# RF315.net
KiCad netlist of a schematic drawn in Altium Designer
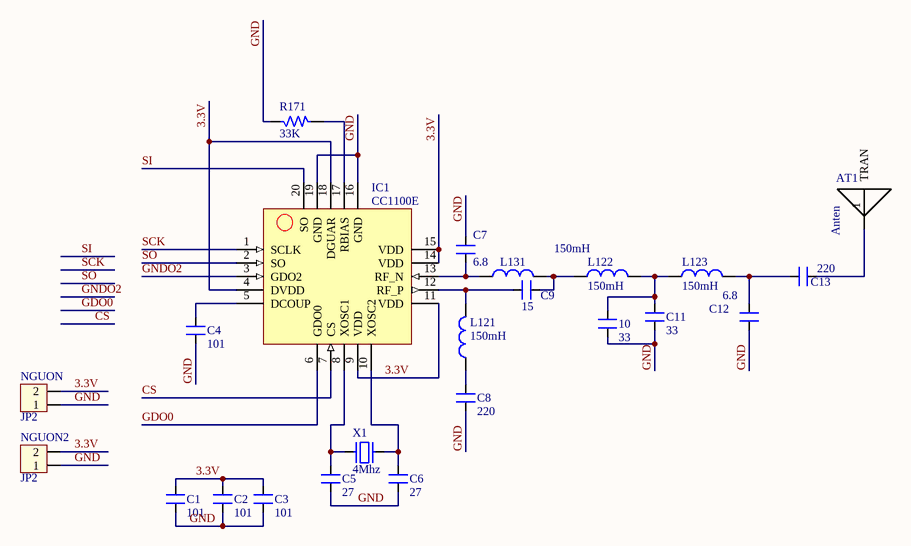
[diagram p0: RF315.SchDoc]

(export (version "E")
  (design (tool "Eeschema 10.0.6"))
  (components
    (comp (ref "10")
      (value "33")
      (footprint "SM-0805")
      (description "Cap SMD")
      (libsource (lib "syhaunguyen") (part "CM"))
    )
    (comp (ref "AT1") (value "Anten") (footprint "VIT") (libsource (lib "Antena") (part "Anten")))
    (comp (ref "C1")
      (value "101")
      (footprint "SM-0805")
      (description "Cap SMD")
      (libsource (lib "syhaunguyen") (part "CM"))
    )
    (comp (ref "C2")
      (value "101")
      (footprint "SM-0805")
      (description "Cap SMD")
      (libsource (lib "syhaunguyen") (part "CM"))
    )
    (comp (ref "C3")
      (value "101")
      (footprint "SM-0805")
      (description "Cap SMD")
      (libsource (lib "syhaunguyen") (part "CM"))
    )
    (comp (ref "C4")
      (value "101")
      (footprint "SM-0805")
      (description "Cap SMD")
      (libsource (lib "syhaunguyen") (part "CM"))
    )
    (comp (ref "C5")
      (value "27")
      (footprint "SM-0805")
      (description "Cap SMD")
      (libsource (lib "syhaunguyen") (part "CM"))
    )
    (comp (ref "C6")
      (value "27")
      (footprint "SM-0805")
      (description "Cap SMD")
      (libsource (lib "syhaunguyen") (part "CM"))
    )
    (comp (ref "C7")
      (value "6.8")
      (footprint "SM-0805")
      (description "Cap SMD")
      (libsource (lib "syhaunguyen") (part "CM"))
    )
    (comp (ref "C8")
      (value "220")
      (footprint "SM-0805")
      (description "Cap SMD")
      (libsource (lib "syhaunguyen") (part "CM"))
    )
    (comp (ref "C9")
      (value "15")
      (footprint "SM-0805")
      (description "Cap SMD")
      (libsource (lib "syhaunguyen") (part "CM"))
    )
    (comp (ref "C11")
      (value "33")
      (footprint "SM-0805")
      (description "Cap SMD")
      (libsource (lib "syhaunguyen") (part "CM"))
    )
    (comp (ref "C12")
      (value "6.8")
      (footprint "SM-0805")
      (description "Cap SMD")
      (libsource (lib "syhaunguyen") (part "CM"))
    )
    (comp (ref "C13")
      (value "220")
      (footprint "SM-0805")
      (description "Cap SMD")
      (libsource (lib "syhaunguyen") (part "CM"))
    )
    (comp (ref "IC1")
      (value "CC1100E")
      (footprint "CC1101-20P:CC1101-20P")
      (libsource (lib "CC1100") (part "CC1100E"))
    )
    (comp (ref "L121")
      (value "150mH")
      (footprint "L/0.4")
      (description "Inductor")
      (libsource (lib "syhaunguyen") (part "L1"))
    )
    (comp (ref "L122")
      (value "150mH")
      (footprint "L/0.4")
      (description "Inductor")
      (libsource (lib "syhaunguyen") (part "L1"))
    )
    (comp (ref "L123")
      (value "150mH")
      (footprint "L/0.4")
      (description "Inductor")
      (libsource (lib "syhaunguyen") (part "L1"))
    )
    (comp (ref "L131")
      (value "150mH")
      (footprint "L/0.4")
      (description "Inductor")
      (libsource (lib "syhaunguyen") (part "L1"))
    )
    (comp (ref "NGUON")
      (value "JP2")
      (footprint "CON2")
      (description "Connector 2")
      (libsource (lib "syhaunguyen") (part "Con2"))
    )
    (comp (ref "NGUON2")
      (value "JP2")
      (footprint "CON2")
      (description "Connector 2")
      (libsource (lib "syhaunguyen") (part "Con2"))
    )
    (comp (ref "R171")
      (value "33K")
      (footprint "SM-0805")
      (description "Resistor 1/4W")
      (libsource (lib "syhaunguyen") (part "R"))
    )
    (comp (ref "X1")
      (value "4Mhz")
      (footprint "CP1/2.5_SM")
      (description "Crystal For all Crystal 2pin.")
      (libsource (lib "syhaunguyen") (part "XT2"))
    )
  )
  (nets
    (net (code "1") (name "/3.3V") (class "Default")
      (node (ref "C1") (pin "1") (pinfunction "1_1") (pintype "passive"))
      (node (ref "C2") (pin "1") (pinfunction "1_1") (pintype "passive"))
      (node (ref "C3") (pin "1") (pinfunction "1_1") (pintype "passive"))
      (node (ref "IC1") (pin "11") (pinfunction "VDD_11") (pintype "power_in"))
      (node (ref "IC1") (pin "14") (pinfunction "VDD_14") (pintype "power_in"))
      (node (ref "IC1") (pin "15") (pinfunction "VDD_15") (pintype "power_in"))
      (node (ref "IC1") (pin "18") (pinfunction "DGUAR_18") (pintype "passive"))
      (node (ref "IC1") (pin "4") (pinfunction "DVDD_4") (pintype "power_in"))
      (node (ref "IC1") (pin "9") (pinfunction "VDD_9") (pintype "power_in"))
      (node (ref "NGUON") (pin "2") (pinfunction "2_2") (pintype "passive"))
      (node (ref "NGUON2") (pin "2") (pinfunction "2_2") (pintype "passive"))
    )
    (net (code "2") (name "/CS") (class "Default")
      (node (ref "IC1") (pin "7") (pinfunction "CS_7") (pintype "input"))
    )
    (net (code "3") (name "/GDO0") (class "Default")
      (node (ref "IC1") (pin "6") (pinfunction "GDO0_6") (pintype "passive"))
    )
    (net (code "4") (name "/GND") (class "Default")
      (node (ref "10") (pin "1") (pinfunction "1_1") (pintype "passive"))
      (node (ref "C1") (pin "2") (pinfunction "2_2") (pintype "passive"))
      (node (ref "C11") (pin "1") (pinfunction "1_1") (pintype "passive"))
      (node (ref "C12") (pin "1") (pinfunction "1_1") (pintype "passive"))
      (node (ref "C2") (pin "2") (pinfunction "2_2") (pintype "passive"))
      (node (ref "C3") (pin "2") (pinfunction "2_2") (pintype "passive"))
      (node (ref "C4") (pin "2") (pinfunction "2_2") (pintype "passive"))
      (node (ref "C5") (pin "2") (pinfunction "2_2") (pintype "passive"))
      (node (ref "C6") (pin "2") (pinfunction "2_2") (pintype "passive"))
      (node (ref "C7") (pin "2") (pinfunction "2_2") (pintype "passive"))
      (node (ref "C8") (pin "1") (pinfunction "1_1") (pintype "passive"))
      (node (ref "IC1") (pin "16") (pinfunction "GND_16") (pintype "power_in"))
      (node (ref "IC1") (pin "19") (pinfunction "GND_19") (pintype "power_in"))
      (node (ref "NGUON") (pin "1") (pinfunction "1_1") (pintype "passive"))
      (node (ref "NGUON2") (pin "1") (pinfunction "1_1") (pintype "passive"))
      (node (ref "R171") (pin "1") (pinfunction "1_1") (pintype "passive"))
    )
    (net (code "5") (name "/GNDO2") (class "Default")
      (node (ref "IC1") (pin "3") (pinfunction "GDO2_3") (pintype "input"))
    )
    (net (code "6") (name "/SCK") (class "Default")
      (node (ref "IC1") (pin "1") (pinfunction "SCLK_1") (pintype "input"))
    )
    (net (code "7") (name "/SI") (class "Default")
      (node (ref "IC1") (pin "20") (pinfunction "SO_20") (pintype "passive"))
    )
    (net (code "8") (name "/SO") (class "Default")
      (node (ref "IC1") (pin "2") (pinfunction "SO_2") (pintype "input"))
    )
    (net (code "9") (name "Net-(10-Pad2)") (class "Default")
      (node (ref "10") (pin "2") (pinfunction "2_2") (pintype "passive"))
      (node (ref "C11") (pin "2") (pinfunction "2_2") (pintype "passive"))
      (node (ref "L122") (pin "2") (pinfunction "2_2") (pintype "passive"))
      (node (ref "L123") (pin "1") (pinfunction "1_1") (pintype "passive"))
    )
    (net (code "10") (name "Net-(AT1-TRAN)") (class "Default")
      (node (ref "AT1") (pin "1") (pinfunction "TRAN_1") (pintype "passive"))
      (node (ref "C13") (pin "1") (pinfunction "1_1") (pintype "passive"))
    )
    (net (code "11") (name "Net-(C8-Pad2)") (class "Default")
      (node (ref "C8") (pin "2") (pinfunction "2_2") (pintype "passive"))
      (node (ref "L121") (pin "1") (pinfunction "1_1") (pintype "passive"))
    )
    (net (code "12") (name "Net-(C9-Pad2)") (class "Default")
      (node (ref "C9") (pin "2") (pinfunction "2_2") (pintype "passive"))
      (node (ref "L122") (pin "1") (pinfunction "1_1") (pintype "passive"))
      (node (ref "L131") (pin "2") (pinfunction "2_2") (pintype "passive"))
    )
    (net (code "13") (name "Net-(C12-Pad2)") (class "Default")
      (node (ref "C12") (pin "2") (pinfunction "2_2") (pintype "passive"))
      (node (ref "C13") (pin "2") (pinfunction "2_2") (pintype "passive"))
      (node (ref "L123") (pin "2") (pinfunction "2_2") (pintype "passive"))
    )
    (net (code "14") (name "Net-(IC1-DCOUP)") (class "Default")
      (node (ref "C4") (pin "1") (pinfunction "1_1") (pintype "passive"))
      (node (ref "IC1") (pin "5") (pinfunction "DCOUP_5") (pintype "passive"))
    )
    (net (code "15") (name "Net-(IC1-RBIAS)") (class "Default")
      (node (ref "IC1") (pin "17") (pinfunction "RBIAS_17") (pintype "passive"))
      (node (ref "R171") (pin "2") (pinfunction "2_2") (pintype "passive"))
    )
    (net (code "16") (name "Net-(IC1-RF_N)") (class "Default")
      (node (ref "C7") (pin "1") (pinfunction "1_1") (pintype "passive"))
      (node (ref "IC1") (pin "13") (pinfunction "RF_N_13") (pintype "input"))
      (node (ref "L131") (pin "1") (pinfunction "1_1") (pintype "passive"))
    )
    (net (code "17") (name "Net-(IC1-RF_P)") (class "Default")
      (node (ref "C9") (pin "1") (pinfunction "1_1") (pintype "passive"))
      (node (ref "IC1") (pin "12") (pinfunction "RF_P_12") (pintype "output"))
      (node (ref "L121") (pin "2") (pinfunction "2_2") (pintype "passive"))
    )
    (net (code "18") (name "Net-(IC1-XOSC1)") (class "Default")
      (node (ref "C5") (pin "1") (pinfunction "1_1") (pintype "passive"))
      (node (ref "IC1") (pin "8") (pinfunction "XOSC1_8") (pintype "passive"))
      (node (ref "X1") (pin "1") (pinfunction "1_1") (pintype "passive"))
    )
    (net (code "19") (name "Net-(IC1-XOSC2)") (class "Default")
      (node (ref "C6") (pin "1") (pinfunction "1_1") (pintype "passive"))
      (node (ref "IC1") (pin "10") (pinfunction "XOSC2_10") (pintype "passive"))
      (node (ref "X1") (pin "2") (pinfunction "2_2") (pintype "passive"))
    )
  )
)
